# 2-VoltProtector_CurrSens.net
KiCad netlist of a schematic drawn in Altium Designer
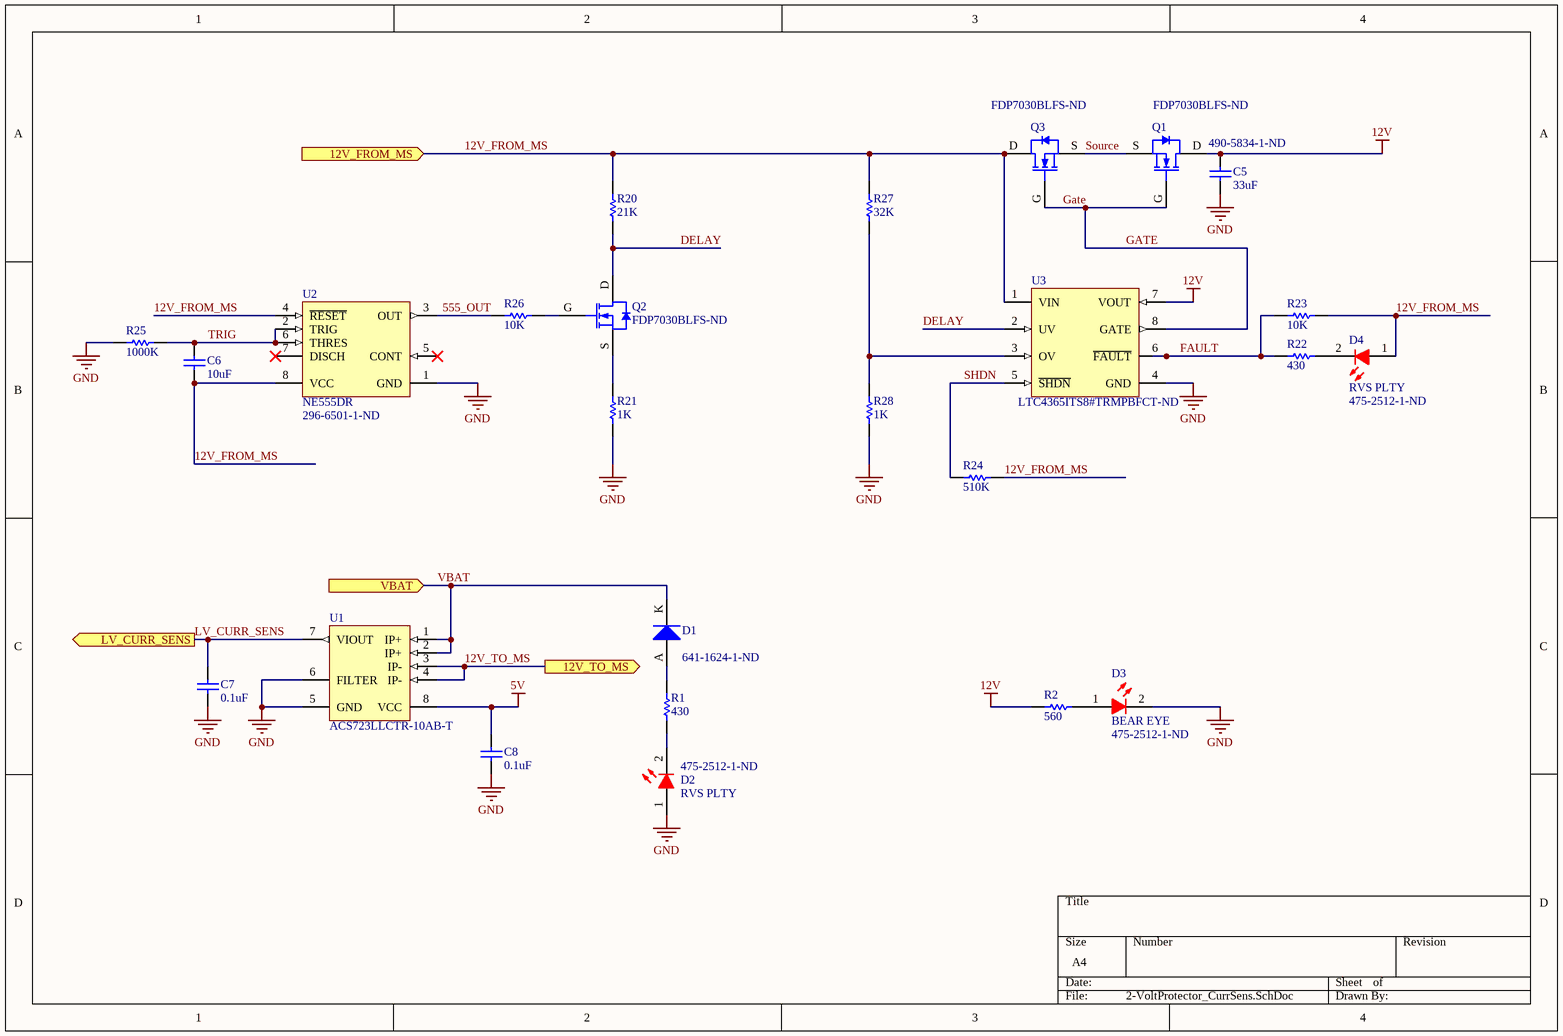
[diagram p0: 2-VoltProtector_CurrSens.SchDoc]

(export (version "E")
  (design (tool "Eeschema 10.0.6"))
  (components
    (comp (ref "C5")
      (value "33uF")
      (footprint "2J-Lead 6.1 x 5.3")
      (description "Capacitor (Semiconductor SIM Model)")
      (fields
        (field (name "SUPPLIER PART NUMBER 1") "490-5834-1-ND")
        (field (name "Comment") "Cap Semi")
        (field (name "PUBLISHER") "Altium Limited")
      )
      (libsource (lib "Miscellaneous Devices") (part "Cap Semi"))
    )
    (comp (ref "C6")
      (value "10uF")
      (footprint "2J-Lead 6.1 x 5.3")
      (description "Capacitor (Semiconductor SIM Model)")
      (fields (field (name "Comment") "Cap Semi") (field (name "PUBLISHER") "Altium Limited"))
      (libsource (lib "Miscellaneous Devices") (part "Cap Semi"))
    )
    (comp (ref "C7")
      (value "0.1uF")
      (footprint "1608[0603]")
      (description "Capacitor (Semiconductor SIM Model)")
      (fields (field (name "Comment") "Cap Semi") (field (name "PUBLISHER") "Altium Limited"))
      (libsource (lib "Miscellaneous Devices") (part "Cap Semi"))
    )
    (comp (ref "C8")
      (value "0.1uF")
      (footprint "1608[0603]")
      (description "Capacitor (Semiconductor SIM Model)")
      (fields (field (name "Comment") "Cap Semi") (field (name "PUBLISHER") "Altium Limited"))
      (libsource (lib "Miscellaneous Devices") (part "Cap Semi"))
    )
    (comp (ref "D1")
      (value "~")
      (footprint "SOD-123")
      (description "1 Amp General Purpose Rectifier")
      (fields
        (field (name "SUPPLIER PART NUMBER 1") "641-1624-1-ND")
        (field (name "PUBLISHER") "Altium Limited")
      )
      (libsource (lib "Miscellaneous Devices") (part "Diode 1N4003"))
    )
    (comp (ref "D2")
      (value "RVS PLTY")
      (footprint "TOSH-0603LED_RED_V")
      (description "LED, Red 0603 (1608) 63mCd")
      (fields
        (field (name "MANUFACTURER") "Toshiba")
        (field (name "PARTNUMBER") "TLSU1008A(T04)")
        (field (name "SUPPLIER PART NUMBER 1") "475-2512-1-ND")
      )
      (libsource (lib "Altium Content Vault") (part "CMP-0444-00001-1"))
    )
    (comp (ref "D3")
      (value "BEAR EYE")
      (footprint "TOSH-0603LED_RED_V")
      (description "LED, Red 0603 (1608) 63mCd")
      (fields
        (field (name "MANUFACTURER") "Toshiba")
        (field (name "PARTNUMBER") "TLSU1008A(T04)")
        (field (name "SUPPLIER PART NUMBER 1") "475-2512-1-ND")
      )
      (libsource (lib "Altium Content Vault") (part "CMP-0444-00001-1"))
    )
    (comp (ref "D4")
      (value "RVS PLTY")
      (footprint "TOSH-0603LED_RED_V")
      (description "LED, Red 0603 (1608) 63mCd")
      (fields
        (field (name "MANUFACTURER") "Toshiba")
        (field (name "PARTNUMBER") "TLSU1008A(T04)")
        (field (name "SUPPLIER PART NUMBER 1") "475-2512-1-ND")
      )
      (libsource (lib "Altium Content Vault") (part "CMP-0444-00001-1"))
    )
    (comp (ref "Q1")
      (value "~")
      (footprint "TO220V-GDS")
      (description "Power MOSFET, 40 V, 167 A, Single N-Channel, 3-Pin TO-220, Pb-Free, Tube")
      (fields (field (name "SUPPLIER PART NUMBER 1") "FDP7030BLFS-ND"))
      (libsource (lib "altium-import") (part "root_1_mirrored_CMP-1058-00860-1_"))
    )
    (comp (ref "Q2")
      (value "~")
      (footprint "TO220V-GDS")
      (description "Power MOSFET, 40 V, 167 A, Single N-Channel, 3-Pin TO-220, Pb-Free, Tube")
      (fields (field (name "SUPPLIER PART NUMBER 1") "FDP7030BLFS-ND"))
      (libsource (lib "altium-import") (part "root_0_CMP-1058-00860-1_"))
    )
    (comp (ref "Q3")
      (value "~")
      (footprint "TO220V-GDS")
      (description "Power MOSFET, 40 V, 167 A, Single N-Channel, 3-Pin TO-220, Pb-Free, Tube")
      (fields (field (name "SUPPLIER PART NUMBER 1") "FDP7030BLFS-ND"))
      (libsource (lib "altium-import") (part "root_1_CMP-1058-00860-1_"))
    )
    (comp (ref "R1")
      (value "430")
      (footprint "RESC0603(1608)_L")
      (description "0603 (1608 Metric) Chip Resistor")
      (libsource (lib "Altium Content Vault") (part "RES_3"))
    )
    (comp (ref "R2")
      (value "560")
      (footprint "RESC0603(1608)_L")
      (description "0603 (1608 Metric) Chip Resistor")
      (libsource (lib "Altium Content Vault") (part "RES_3"))
    )
    (comp (ref "R20")
      (value "21K")
      (footprint "RESC0603(1608)_L")
      (description "0603 (1608 Metric) Chip Resistor")
      (libsource (lib "Altium Content Vault") (part "RES_3"))
    )
    (comp (ref "R21")
      (value "1K")
      (footprint "RESC0603(1608)_L")
      (description "0603 (1608 Metric) Chip Resistor")
      (libsource (lib "Altium Content Vault") (part "RES_3"))
    )
    (comp (ref "R22")
      (value "430")
      (footprint "RESC0603(1608)_L")
      (description "0603 (1608 Metric) Chip Resistor")
      (libsource (lib "Altium Content Vault") (part "RES_3"))
    )
    (comp (ref "R23")
      (value "10K")
      (footprint "RESC0603(1608)_L")
      (description "0603 (1608 Metric) Chip Resistor")
      (libsource (lib "Altium Content Vault") (part "RES_3"))
    )
    (comp (ref "R24")
      (value "510K")
      (footprint "RESC0603(1608)_L")
      (description "0603 (1608 Metric) Chip Resistor")
      (libsource (lib "Altium Content Vault") (part "RES_3"))
    )
    (comp (ref "R25")
      (value "1000K")
      (footprint "RESC0603(1608)_L")
      (description "0603 (1608 Metric) Chip Resistor")
      (libsource (lib "Altium Content Vault") (part "RES_3"))
    )
    (comp (ref "R26")
      (value "10K")
      (footprint "RESC0603(1608)_L")
      (description "0603 (1608 Metric) Chip Resistor")
      (libsource (lib "Altium Content Vault") (part "RES_3"))
    )
    (comp (ref "R27")
      (value "32K")
      (footprint "RESC0603(1608)_L")
      (description "0603 (1608 Metric) Chip Resistor")
      (libsource (lib "Altium Content Vault") (part "RES_3"))
    )
    (comp (ref "R28")
      (value "1K")
      (footprint "RESC0603(1608)_L")
      (description "0603 (1608 Metric) Chip Resistor")
      (libsource (lib "Altium Content Vault") (part "RES_3"))
    )
    (comp (ref "U1")
      (value "ACS723LLCTR-10AB-T")
      (footprint "ALEG-LC-8_V")
      (fields
        (field (name "MANUFACTURER") "Allegro Microsystems")
        (field (name "PARTNUMBER") "ACS712ELCTR-20A-T")
      )
      (libsource (lib "Altium Content Vault") (part "CMP-0826-00001-1"))
    )
    (comp (ref "U2")
      (value "NE555DR")
      (footprint "D0008A_M")
      (fields (field (name "SUPPLIER PART NUMBER 1") "296-6501-1-ND"))
      (libsource (lib "Altium Content Vault") (part "CMP-1685-00007-1"))
    )
    (comp (ref "U3")
      (value "LTC4365ITS8#TRMPBF")
      (footprint "LT-TS8-8-TSOT-23_V")
      (fields
        (field (name "MANUFACTURER") "Linear Technology")
        (field (name "SUPPLIER PART NUMBER 1") "LTC4365ITS8#TRMPBFCT-ND")
      )
      (libsource (lib "Altium Content Vault") (part "LT-LTC4365-TS8-8"))
    )
  )
  (nets
    (net (code "1") (name "/12V_FROM_MS") (class "Default")
      (node (ref "C6") (pin "2") (pinfunction "2_2") (pintype "passive"))
      (node (ref "D4") (pin "1") (pinfunction "A_1") (pintype "passive"))
      (node (ref "Q3") (pin "D") (pinfunction "D_D") (pintype "passive"))
      (node (ref "R20") (pin "1") (pinfunction "1_1") (pintype "passive"))
      (node (ref "R23") (pin "1") (pinfunction "1_1") (pintype "passive"))
      (node (ref "R24") (pin "1") (pinfunction "1_1") (pintype "passive"))
      (node (ref "R27") (pin "2") (pinfunction "2_2") (pintype "passive"))
      (node (ref "U2") (pin "4") (pinfunction "~{RESET}_4") (pintype "input"))
      (node (ref "U2") (pin "8") (pinfunction "VCC_8") (pintype "power_in"))
      (node (ref "U3") (pin "1") (pinfunction "VIN_1") (pintype "power_in"))
    )
    (net (code "2") (name "/12V_TO_MS") (class "Default")
      (node (ref "U1") (pin "3") (pinfunction "IP-_3") (pintype "input"))
      (node (ref "U1") (pin "4") (pinfunction "IP-_4") (pintype "input"))
    )
    (net (code "3") (name "/555_OUT") (class "Default")
      (node (ref "R26") (pin "2") (pinfunction "2_2") (pintype "passive"))
      (node (ref "U2") (pin "3") (pinfunction "OUT_3") (pintype "output"))
    )
    (net (code "4") (name "/DELAY") (class "Default")
      (node (ref "Q2") (pin "D") (pinfunction "D_D") (pintype "passive"))
      (node (ref "R20") (pin "2") (pinfunction "2_2") (pintype "passive"))
      (node (ref "U3") (pin "2") (pinfunction "UV_2") (pintype "input"))
    )
    (net (code "5") (name "/FAULT") (class "Default")
      (node (ref "R22") (pin "1") (pinfunction "1_1") (pintype "passive"))
      (node (ref "R23") (pin "2") (pinfunction "2_2") (pintype "passive"))
      (node (ref "U3") (pin "6") (pinfunction "~{FAULT}_6") (pintype "open_collector"))
    )
    (net (code "6") (name "/GATE") (class "Default")
      (node (ref "Q1") (pin "G") (pinfunction "G_G") (pintype "passive"))
      (node (ref "Q3") (pin "G") (pinfunction "G_G") (pintype "passive"))
      (node (ref "U3") (pin "8") (pinfunction "GATE_8") (pintype "output"))
    )
    (net (code "7") (name "/LV_CURR_SENS") (class "Default")
      (node (ref "C7") (pin "2") (pinfunction "2_2") (pintype "passive"))
      (node (ref "U1") (pin "7") (pinfunction "VIOUT_7") (pintype "output"))
    )
    (net (code "8") (name "/SHDN") (class "Default")
      (node (ref "R24") (pin "2") (pinfunction "2_2") (pintype "passive"))
      (node (ref "U3") (pin "5") (pinfunction "~{SHDN}_5") (pintype "input"))
    )
    (net (code "9") (name "/Source") (class "Default")
      (node (ref "Q1") (pin "S") (pinfunction "S_S") (pintype "passive"))
      (node (ref "Q3") (pin "S") (pinfunction "S_S") (pintype "passive"))
    )
    (net (code "10") (name "/TRIG") (class "Default")
      (node (ref "C6") (pin "1") (pinfunction "1_1") (pintype "passive"))
      (node (ref "R25") (pin "1") (pinfunction "1_1") (pintype "passive"))
      (node (ref "U2") (pin "2") (pinfunction "TRIG_2") (pintype "input"))
      (node (ref "U2") (pin "6") (pinfunction "THRES_6") (pintype "input"))
    )
    (net (code "11") (name "/VBAT") (class "Default")
      (node (ref "D1") (pin "K") (pinfunction "K_K") (pintype "passive"))
      (node (ref "U1") (pin "1") (pinfunction "IP+_1") (pintype "input"))
      (node (ref "U1") (pin "2") (pinfunction "IP+_2") (pintype "input"))
    )
    (net (code "12") (name "5V") (class "Default")
      (node (ref "C8") (pin "2") (pinfunction "2_2") (pintype "passive"))
      (node (ref "U1") (pin "8") (pinfunction "VCC_8") (pintype "power_in"))
    )
    (net (code "13") (name "12V") (class "Default")
      (node (ref "C5") (pin "1") (pinfunction "1_1") (pintype "passive"))
      (node (ref "Q1") (pin "D") (pinfunction "D_D") (pintype "passive"))
      (node (ref "R2") (pin "1") (pinfunction "1_1") (pintype "passive"))
      (node (ref "U3") (pin "7") (pinfunction "VOUT_7") (pintype "input"))
    )
    (net (code "14") (name "GND") (class "Default")
      (node (ref "C5") (pin "2") (pinfunction "2_2") (pintype "passive"))
      (node (ref "C7") (pin "1") (pinfunction "1_1") (pintype "passive"))
      (node (ref "C8") (pin "1") (pinfunction "1_1") (pintype "passive"))
      (node (ref "D2") (pin "1") (pinfunction "A_1") (pintype "passive"))
      (node (ref "D3") (pin "2") (pinfunction "K_2") (pintype "passive"))
      (node (ref "R21") (pin "2") (pinfunction "2_2") (pintype "passive"))
      (node (ref "R25") (pin "2") (pinfunction "2_2") (pintype "passive"))
      (node (ref "R28") (pin "1") (pinfunction "1_1") (pintype "passive"))
      (node (ref "U1") (pin "5") (pinfunction "GND_5") (pintype "power_in"))
      (node (ref "U1") (pin "6") (pinfunction "FILTER_6") (pintype "passive"))
      (node (ref "U2") (pin "1") (pinfunction "GND_1") (pintype "power_in"))
      (node (ref "U3") (pin "4") (pinfunction "GND_4") (pintype "power_in"))
    )
    (net (code "15") (name "Net-(D1-PadA)") (class "Default")
      (node (ref "D1") (pin "A") (pinfunction "A_A") (pintype "passive"))
      (node (ref "R1") (pin "2") (pinfunction "2_2") (pintype "passive"))
    )
    (net (code "16") (name "Net-(D2-K)") (class "Default")
      (node (ref "D2") (pin "2") (pinfunction "K_2") (pintype "passive"))
      (node (ref "R1") (pin "1") (pinfunction "1_1") (pintype "passive"))
    )
    (net (code "17") (name "Net-(D3-A)") (class "Default")
      (node (ref "D3") (pin "1") (pinfunction "A_1") (pintype "passive"))
      (node (ref "R2") (pin "2") (pinfunction "2_2") (pintype "passive"))
    )
    (net (code "18") (name "Net-(D4-K)") (class "Default")
      (node (ref "D4") (pin "2") (pinfunction "K_2") (pintype "passive"))
      (node (ref "R22") (pin "2") (pinfunction "2_2") (pintype "passive"))
    )
    (net (code "19") (name "Net-(Q2-PadG)") (class "Default")
      (node (ref "Q2") (pin "G") (pinfunction "G_G") (pintype "passive"))
      (node (ref "R26") (pin "1") (pinfunction "1_1") (pintype "passive"))
    )
    (net (code "20") (name "Net-(Q2-PadS)") (class "Default")
      (node (ref "Q2") (pin "S") (pinfunction "S_S") (pintype "passive"))
      (node (ref "R21") (pin "1") (pinfunction "1_1") (pintype "passive"))
    )
    (net (code "21") (name "Net-(U3-OV)") (class "Default")
      (node (ref "R27") (pin "1") (pinfunction "1_1") (pintype "passive"))
      (node (ref "R28") (pin "2") (pinfunction "2_2") (pintype "passive"))
      (node (ref "U3") (pin "3") (pinfunction "OV_3") (pintype "input"))
    )
    (net (code "22") (name "unconnected-(U2-CONT-Pad5)") (class "Default")
      (node (ref "U2") (pin "5") (pinfunction "CONT_5") (pintype "input+no_connect"))
    )
    (net (code "23") (name "unconnected-(U2-DISCH-Pad7)") (class "Default")
      (node (ref "U2") (pin "7") (pinfunction "DISCH_7") (pintype "open_collector+no_connect"))
    )
  )
)
